# reamiga_1200_mouse_USB_v1.net
KiCad netlist of a schematic drawn in EAGLE
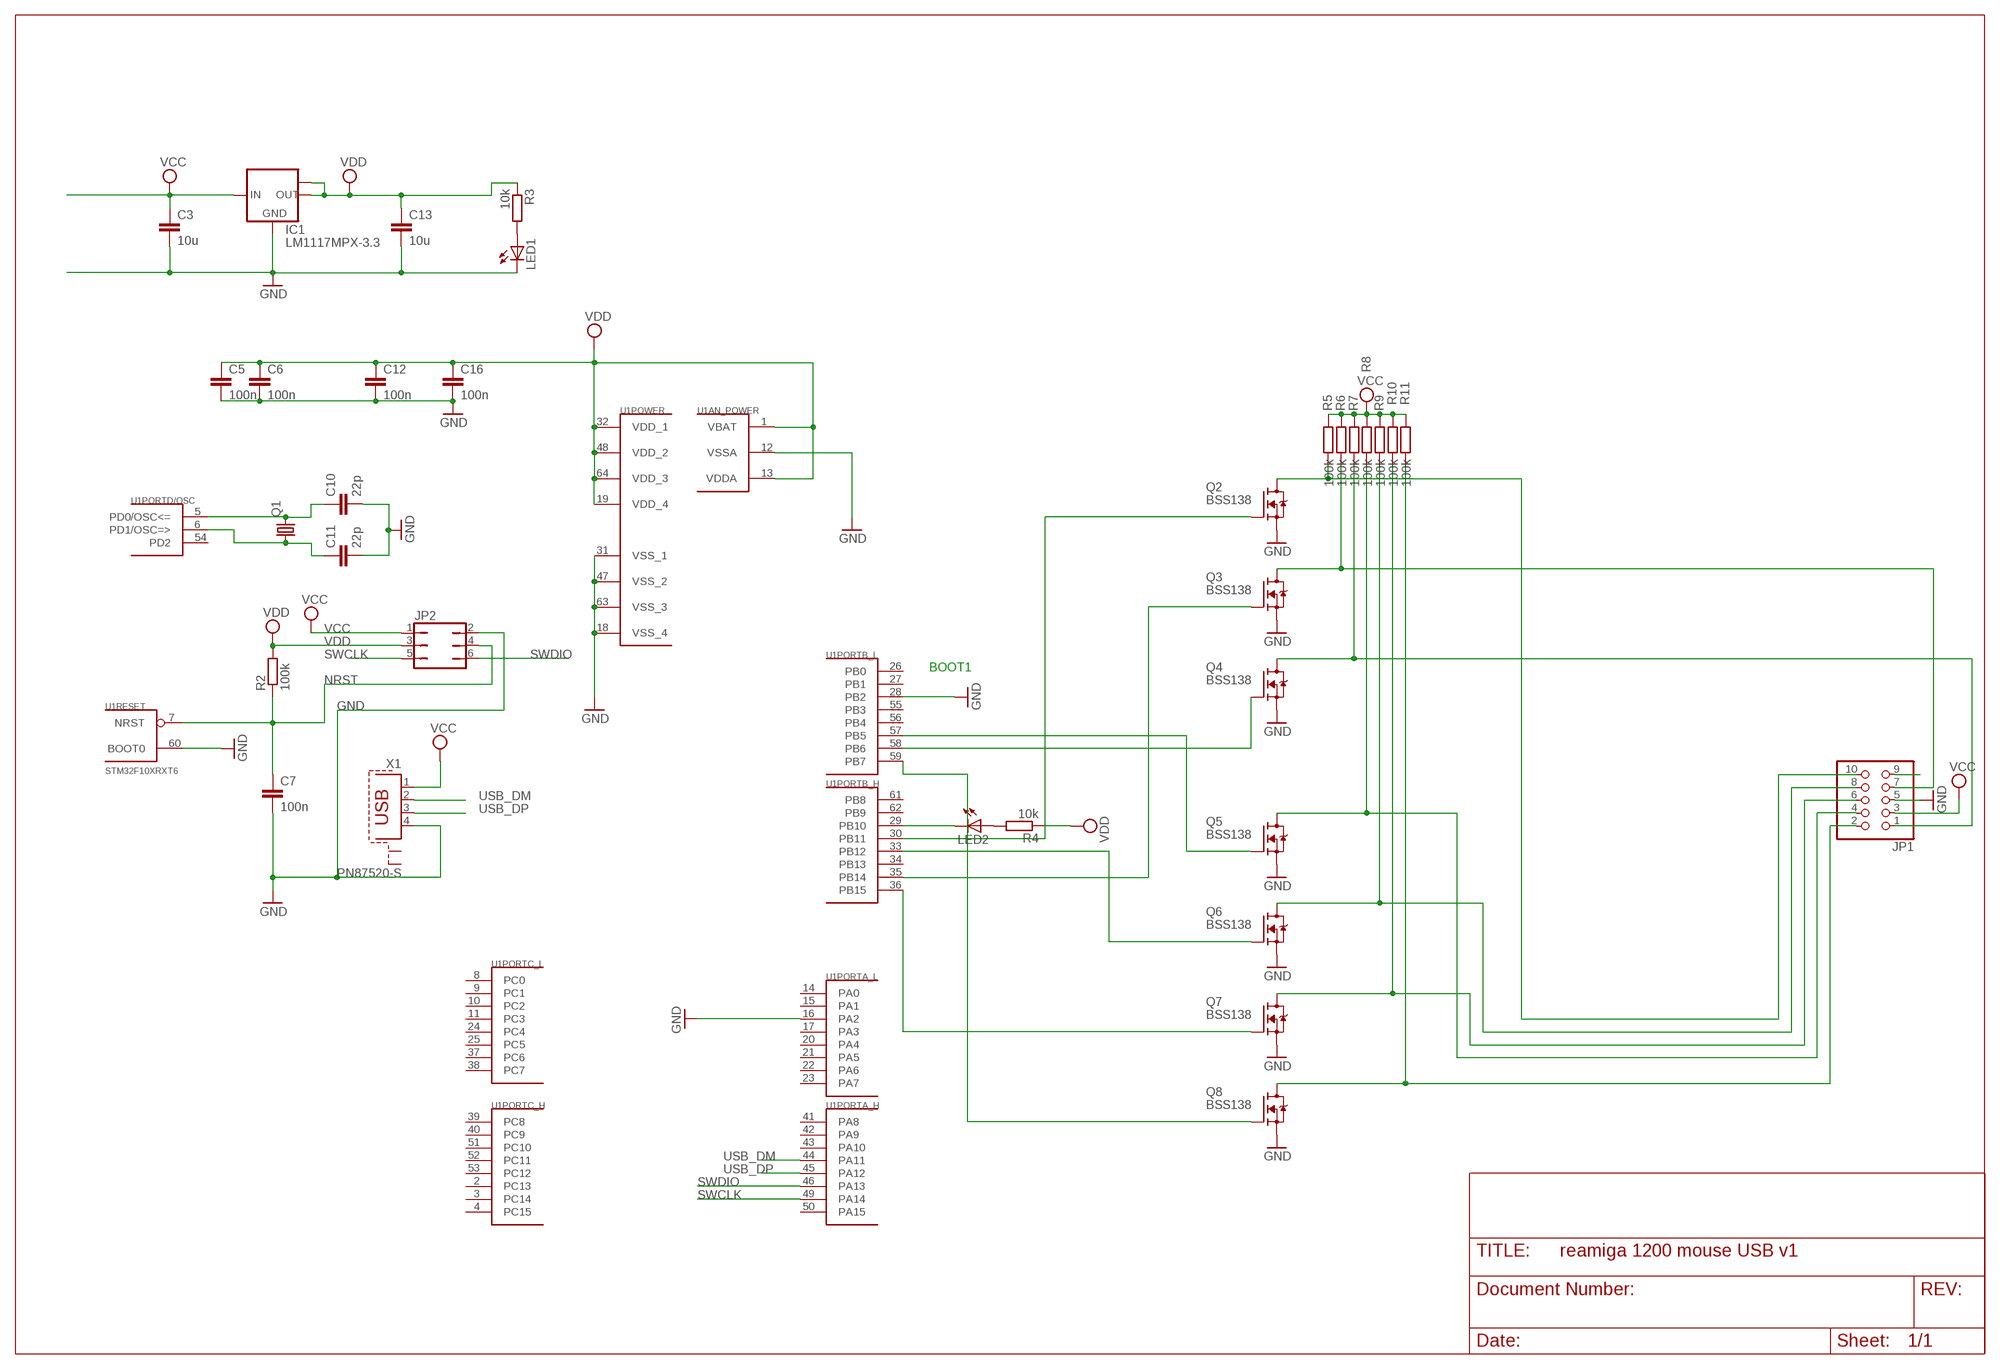
[diagram p0: schematic, sheet 1]

(export (version "E")
  (design (tool "Eeschema 10.0.6"))
  (components
    (comp (ref "C3")
      (value "10u")
      (footprint "eagle-import:C1206")
      (libsource (lib "eagle-import") (part "C-EUC1206"))
    )
    (comp (ref "C5")
      (value "100n")
      (footprint "eagle-import:C0603")
      (libsource (lib "eagle-import") (part "C-EUC0603"))
    )
    (comp (ref "C6")
      (value "100n")
      (footprint "eagle-import:C0603")
      (libsource (lib "eagle-import") (part "C-EUC0603"))
    )
    (comp (ref "C7")
      (value "100n")
      (footprint "eagle-import:C0603")
      (libsource (lib "eagle-import") (part "C-EUC0603"))
    )
    (comp (ref "C10")
      (value "22p")
      (footprint "eagle-import:C0603")
      (libsource (lib "eagle-import") (part "C-EUC0603"))
    )
    (comp (ref "C11")
      (value "22p")
      (footprint "eagle-import:C0603")
      (libsource (lib "eagle-import") (part "C-EUC0603"))
    )
    (comp (ref "C12")
      (value "100n")
      (footprint "eagle-import:C0603")
      (libsource (lib "eagle-import") (part "C-EUC0603"))
    )
    (comp (ref "C13")
      (value "10u")
      (footprint "eagle-import:C1206")
      (libsource (lib "eagle-import") (part "C-EUC1206"))
    )
    (comp (ref "C16")
      (value "100n")
      (footprint "eagle-import:C0603")
      (libsource (lib "eagle-import") (part "C-EUC0603"))
    )
    (comp (ref "IC1")
      (value "LM1117MPX-3.3")
      (footprint "eagle-import:SOT223")
      (libsource (lib "eagle-import") (part "LM1117MPX-3.3"))
    )
    (comp (ref "JP1")
      (value "PINHD-2X5")
      (footprint "eagle-import:2X05")
      (libsource (lib "eagle-import") (part "PINHD-2X5"))
    )
    (comp (ref "JP2")
      (value "JP3Q")
      (footprint "eagle-import:JP3Q")
      (libsource (lib "eagle-import") (part "JP3Q"))
    )
    (comp (ref "LED1")
      (value "LEDSML0805")
      (footprint "eagle-import:SML0805")
      (libsource (lib "eagle-import") (part "LEDSML0805"))
    )
    (comp (ref "LED2")
      (value "LEDSML0805")
      (footprint "eagle-import:SML0805")
      (libsource (lib "eagle-import") (part "LEDSML0805"))
    )
    (comp (ref "Q1")
      (value "CRYSTALHC49S")
      (footprint "eagle-import:HC49_S")
      (libsource (lib "eagle-import") (part "CRYSTALHC49S"))
    )
    (comp (ref "Q2")
      (value "BSS138")
      (footprint "eagle-import:SOT23")
      (fields (field (name "MF") "Fairchild"))
      (libsource (lib "eagle-import") (part "BSS138"))
    )
    (comp (ref "Q3")
      (value "BSS138")
      (footprint "eagle-import:SOT23")
      (fields (field (name "MF") "Fairchild"))
      (libsource (lib "eagle-import") (part "BSS138"))
    )
    (comp (ref "Q4")
      (value "BSS138")
      (footprint "eagle-import:SOT23")
      (fields (field (name "MF") "Fairchild"))
      (libsource (lib "eagle-import") (part "BSS138"))
    )
    (comp (ref "Q5")
      (value "BSS138")
      (footprint "eagle-import:SOT23")
      (fields (field (name "MF") "Fairchild"))
      (libsource (lib "eagle-import") (part "BSS138"))
    )
    (comp (ref "Q6")
      (value "BSS138")
      (footprint "eagle-import:SOT23")
      (fields (field (name "MF") "Fairchild"))
      (libsource (lib "eagle-import") (part "BSS138"))
    )
    (comp (ref "Q7")
      (value "BSS138")
      (footprint "eagle-import:SOT23")
      (fields (field (name "MF") "Fairchild"))
      (libsource (lib "eagle-import") (part "BSS138"))
    )
    (comp (ref "Q8")
      (value "BSS138")
      (footprint "eagle-import:SOT23")
      (fields (field (name "MF") "Fairchild"))
      (libsource (lib "eagle-import") (part "BSS138"))
    )
    (comp (ref "R2")
      (value "100k")
      (footprint "eagle-import:R0603")
      (libsource (lib "eagle-import") (part "R-EU_R0603"))
    )
    (comp (ref "R3")
      (value "10k")
      (footprint "eagle-import:R0603")
      (libsource (lib "eagle-import") (part "R-EU_R0603"))
    )
    (comp (ref "R4")
      (value "10k")
      (footprint "eagle-import:R0603")
      (libsource (lib "eagle-import") (part "R-EU_R0603"))
    )
    (comp (ref "R5")
      (value "100k")
      (footprint "eagle-import:R0603")
      (libsource (lib "eagle-import") (part "R-EU_R0603"))
    )
    (comp (ref "R6")
      (value "100k")
      (footprint "eagle-import:R0603")
      (libsource (lib "eagle-import") (part "R-EU_R0603"))
    )
    (comp (ref "R7")
      (value "100k")
      (footprint "eagle-import:R0603")
      (libsource (lib "eagle-import") (part "R-EU_R0603"))
    )
    (comp (ref "R8")
      (value "100k")
      (footprint "eagle-import:R0603")
      (libsource (lib "eagle-import") (part "R-EU_R0603"))
    )
    (comp (ref "R9")
      (value "100k")
      (footprint "eagle-import:R0603")
      (libsource (lib "eagle-import") (part "R-EU_R0603"))
    )
    (comp (ref "R10")
      (value "100k")
      (footprint "eagle-import:R0603")
      (libsource (lib "eagle-import") (part "R-EU_R0603"))
    )
    (comp (ref "R11")
      (value "100k")
      (footprint "eagle-import:R0603")
      (libsource (lib "eagle-import") (part "R-EU_R0603"))
    )
    (comp (ref "U1")
      (value "STM32F10XRXT6")
      (footprint "eagle-import:TQFP64")
      (libsource (lib "eagle-import") (part "STM32F10XRXT6"))
    )
    (comp (ref "X1")
      (value "PN87520-S")
      (footprint "eagle-import:PN87520-S")
      (libsource (lib "eagle-import") (part "PN87520-S"))
    )
  )
  (nets
    (net (code "1") (name "/NRST") (class "Default")
      (node (ref "C7") (pin "1") (pinfunction "1_1") (pintype "passive"))
      (node (ref "JP2") (pin "4") (pinfunction "4_4") (pintype "passive"))
      (node (ref "R2") (pin "1") (pinfunction "1_1") (pintype "passive"))
      (node (ref "U1") (pin "7") (pinfunction "NRST_7") (pintype "input"))
    )
    (net (code "2") (name "/SWCLK") (class "Default")
      (node (ref "JP2") (pin "5") (pinfunction "5_5") (pintype "passive"))
      (node (ref "U1") (pin "49") (pinfunction "PA14_49") (pintype "bidirectional"))
    )
    (net (code "3") (name "/SWDIO") (class "Default")
      (node (ref "JP2") (pin "6") (pinfunction "6_6") (pintype "passive"))
      (node (ref "U1") (pin "46") (pinfunction "PA13_46") (pintype "bidirectional"))
    )
    (net (code "4") (name "/USB_DM") (class "Default")
      (node (ref "U1") (pin "44") (pinfunction "PA11_44") (pintype "bidirectional"))
      (node (ref "X1") (pin "2") (pinfunction "2_2") (pintype "passive"))
    )
    (net (code "5") (name "/USB_DP") (class "Default")
      (node (ref "U1") (pin "45") (pinfunction "PA12_45") (pintype "bidirectional"))
      (node (ref "X1") (pin "3") (pinfunction "3_3") (pintype "passive"))
    )
    (net (code "6") (name "GND") (class "Default")
      (node (ref "C10") (pin "2") (pinfunction "2_2") (pintype "passive"))
      (node (ref "C11") (pin "2") (pinfunction "2_2") (pintype "passive"))
      (node (ref "C12") (pin "2") (pinfunction "2_2") (pintype "passive"))
      (node (ref "C13") (pin "2") (pinfunction "2_2") (pintype "passive"))
      (node (ref "C16") (pin "2") (pinfunction "2_2") (pintype "passive"))
      (node (ref "C3") (pin "2") (pinfunction "2_2") (pintype "passive"))
      (node (ref "C5") (pin "2") (pinfunction "2_2") (pintype "passive"))
      (node (ref "C6") (pin "2") (pinfunction "2_2") (pintype "passive"))
      (node (ref "C7") (pin "2") (pinfunction "2_2") (pintype "passive"))
      (node (ref "IC1") (pin "1") (pinfunction "GND_1") (pintype "input"))
      (node (ref "JP1") (pin "5") (pinfunction "5_5") (pintype "passive"))
      (node (ref "JP2") (pin "2") (pinfunction "2_2") (pintype "passive"))
      (node (ref "LED1") (pin "C") (pinfunction "C_C") (pintype "passive"))
      (node (ref "Q2") (pin "2") (pinfunction "S_2") (pintype "passive"))
      (node (ref "Q3") (pin "2") (pinfunction "S_2") (pintype "passive"))
      (node (ref "Q4") (pin "2") (pinfunction "S_2") (pintype "passive"))
      (node (ref "Q5") (pin "2") (pinfunction "S_2") (pintype "passive"))
      (node (ref "Q6") (pin "2") (pinfunction "S_2") (pintype "passive"))
      (node (ref "Q7") (pin "2") (pinfunction "S_2") (pintype "passive"))
      (node (ref "Q8") (pin "2") (pinfunction "S_2") (pintype "passive"))
      (node (ref "U1") (pin "12") (pinfunction "VSSA_12") (pintype "power_in"))
      (node (ref "U1") (pin "16") (pinfunction "PA2_16") (pintype "bidirectional"))
      (node (ref "U1") (pin "18") (pinfunction "VSS_4_18") (pintype "power_in"))
      (node (ref "U1") (pin "28") (pinfunction "PB2_28") (pintype "bidirectional"))
      (node (ref "U1") (pin "31") (pinfunction "VSS_1_31") (pintype "power_in"))
      (node (ref "U1") (pin "47") (pinfunction "VSS_2_47") (pintype "power_in"))
      (node (ref "U1") (pin "60") (pinfunction "BOOT0_60") (pintype "input"))
      (node (ref "U1") (pin "63") (pinfunction "VSS_3_63") (pintype "power_in"))
      (node (ref "X1") (pin "4") (pinfunction "4_4") (pintype "passive"))
    )
    (net (code "7") (name "Net-(LED1-PadA)") (class "Default")
      (node (ref "LED1") (pin "A") (pinfunction "A_A") (pintype "passive"))
      (node (ref "R3") (pin "2") (pinfunction "2_2") (pintype "passive"))
    )
    (net (code "8") (name "Net-(LED2-PadA)") (class "Default")
      (node (ref "LED2") (pin "A") (pinfunction "A_A") (pintype "passive"))
      (node (ref "R4") (pin "2") (pinfunction "2_2") (pintype "passive"))
    )
    (net (code "9") (name "Net-(Q2-D)") (class "Default")
      (node (ref "JP1") (pin "10") (pinfunction "10_10") (pintype "passive"))
      (node (ref "Q2") (pin "3") (pinfunction "D_3") (pintype "passive"))
      (node (ref "R5") (pin "2") (pinfunction "2_2") (pintype "passive"))
    )
    (net (code "10") (name "Net-(Q2-G)") (class "Default")
      (node (ref "Q2") (pin "1") (pinfunction "G_1") (pintype "passive"))
      (node (ref "U1") (pin "30") (pinfunction "PB11_30") (pintype "bidirectional"))
    )
    (net (code "11") (name "Net-(Q3-D)") (class "Default")
      (node (ref "JP1") (pin "7") (pinfunction "7_7") (pintype "passive"))
      (node (ref "Q3") (pin "3") (pinfunction "D_3") (pintype "passive"))
      (node (ref "R6") (pin "2") (pinfunction "2_2") (pintype "passive"))
    )
    (net (code "12") (name "Net-(Q3-G)") (class "Default")
      (node (ref "Q3") (pin "1") (pinfunction "G_1") (pintype "passive"))
      (node (ref "U1") (pin "35") (pinfunction "PB14_35") (pintype "bidirectional"))
    )
    (net (code "13") (name "Net-(Q4-D)") (class "Default")
      (node (ref "JP1") (pin "1") (pinfunction "1_1") (pintype "passive"))
      (node (ref "Q4") (pin "3") (pinfunction "D_3") (pintype "passive"))
      (node (ref "R7") (pin "2") (pinfunction "2_2") (pintype "passive"))
    )
    (net (code "14") (name "Net-(Q4-G)") (class "Default")
      (node (ref "Q4") (pin "1") (pinfunction "G_1") (pintype "passive"))
      (node (ref "U1") (pin "58") (pinfunction "PB6_58") (pintype "bidirectional"))
    )
    (net (code "15") (name "Net-(Q5-D)") (class "Default")
      (node (ref "JP1") (pin "4") (pinfunction "4_4") (pintype "passive"))
      (node (ref "Q5") (pin "3") (pinfunction "D_3") (pintype "passive"))
      (node (ref "R8") (pin "2") (pinfunction "2_2") (pintype "passive"))
    )
    (net (code "16") (name "Net-(Q5-G)") (class "Default")
      (node (ref "Q5") (pin "1") (pinfunction "G_1") (pintype "passive"))
      (node (ref "U1") (pin "57") (pinfunction "PB5_57") (pintype "bidirectional"))
    )
    (net (code "17") (name "Net-(Q6-D)") (class "Default")
      (node (ref "JP1") (pin "8") (pinfunction "8_8") (pintype "passive"))
      (node (ref "Q6") (pin "3") (pinfunction "D_3") (pintype "passive"))
      (node (ref "R9") (pin "2") (pinfunction "2_2") (pintype "passive"))
    )
    (net (code "18") (name "Net-(Q6-G)") (class "Default")
      (node (ref "Q6") (pin "1") (pinfunction "G_1") (pintype "passive"))
      (node (ref "U1") (pin "33") (pinfunction "PB12_33") (pintype "bidirectional"))
    )
    (net (code "19") (name "Net-(Q7-D)") (class "Default")
      (node (ref "JP1") (pin "6") (pinfunction "6_6") (pintype "passive"))
      (node (ref "Q7") (pin "3") (pinfunction "D_3") (pintype "passive"))
      (node (ref "R10") (pin "2") (pinfunction "2_2") (pintype "passive"))
    )
    (net (code "20") (name "Net-(Q7-G)") (class "Default")
      (node (ref "Q7") (pin "1") (pinfunction "G_1") (pintype "passive"))
      (node (ref "U1") (pin "36") (pinfunction "PB15_36") (pintype "bidirectional"))
    )
    (net (code "21") (name "Net-(Q8-D)") (class "Default")
      (node (ref "JP1") (pin "2") (pinfunction "2_2") (pintype "passive"))
      (node (ref "Q8") (pin "3") (pinfunction "D_3") (pintype "passive"))
      (node (ref "R11") (pin "2") (pinfunction "2_2") (pintype "passive"))
    )
    (net (code "22") (name "Net-(Q8-G)") (class "Default")
      (node (ref "Q8") (pin "1") (pinfunction "G_1") (pintype "passive"))
      (node (ref "U1") (pin "59") (pinfunction "PB7_59") (pintype "bidirectional"))
    )
    (net (code "23") (name "Net-(U1D-PB10)") (class "Default")
      (node (ref "LED2") (pin "C") (pinfunction "C_C") (pintype "passive"))
      (node (ref "U1") (pin "29") (pinfunction "PB10_29") (pintype "bidirectional"))
    )
    (net (code "24") (name "Net-(U1H-PD0{slash}OSC<=)") (class "Default")
      (node (ref "C10") (pin "1") (pinfunction "1_1") (pintype "passive"))
      (node (ref "Q1") (pin "2") (pinfunction "2_2") (pintype "passive"))
      (node (ref "U1") (pin "5") (pinfunction "PD0/OSC<=_5") (pintype "bidirectional"))
    )
    (net (code "25") (name "Net-(U1H-PD1{slash}OSC=>)") (class "Default")
      (node (ref "C11") (pin "1") (pinfunction "1_1") (pintype "passive"))
      (node (ref "Q1") (pin "1") (pinfunction "1_1") (pintype "passive"))
      (node (ref "U1") (pin "6") (pinfunction "PD1/OSC=>_6") (pintype "bidirectional"))
    )
    (net (code "26") (name "VCC") (class "Default")
      (node (ref "C3") (pin "1") (pinfunction "1_1") (pintype "passive"))
      (node (ref "IC1") (pin "3") (pinfunction "IN_3") (pintype "input"))
      (node (ref "JP1") (pin "3") (pinfunction "3_3") (pintype "passive"))
      (node (ref "JP2") (pin "1") (pinfunction "1_1") (pintype "passive"))
      (node (ref "R10") (pin "1") (pinfunction "1_1") (pintype "passive"))
      (node (ref "R11") (pin "1") (pinfunction "1_1") (pintype "passive"))
      (node (ref "R5") (pin "1") (pinfunction "1_1") (pintype "passive"))
      (node (ref "R6") (pin "1") (pinfunction "1_1") (pintype "passive"))
      (node (ref "R7") (pin "1") (pinfunction "1_1") (pintype "passive"))
      (node (ref "R8") (pin "1") (pinfunction "1_1") (pintype "passive"))
      (node (ref "R9") (pin "1") (pinfunction "1_1") (pintype "passive"))
      (node (ref "X1") (pin "1") (pinfunction "1_1") (pintype "passive"))
    )
    (net (code "27") (name "VDD") (class "Default")
      (node (ref "C12") (pin "1") (pinfunction "1_1") (pintype "passive"))
      (node (ref "C13") (pin "1") (pinfunction "1_1") (pintype "passive"))
      (node (ref "C16") (pin "1") (pinfunction "1_1") (pintype "passive"))
      (node (ref "C5") (pin "1") (pinfunction "1_1") (pintype "passive"))
      (node (ref "C6") (pin "1") (pinfunction "1_1") (pintype "passive"))
      (node (ref "IC1") (pin "2") (pinfunction "OUT_2") (pintype "passive"))
      (node (ref "IC1") (pin "TAB") (pinfunction "OUT1_TAB") (pintype "passive"))
      (node (ref "JP2") (pin "3") (pinfunction "3_3") (pintype "passive"))
      (node (ref "R2") (pin "2") (pinfunction "2_2") (pintype "passive"))
      (node (ref "R3") (pin "1") (pinfunction "1_1") (pintype "passive"))
      (node (ref "R4") (pin "1") (pinfunction "1_1") (pintype "passive"))
      (node (ref "U1") (pin "1") (pinfunction "VBAT_1") (pintype "power_in"))
      (node (ref "U1") (pin "13") (pinfunction "VDDA_13") (pintype "power_in"))
      (node (ref "U1") (pin "19") (pinfunction "VDD_4_19") (pintype "power_in"))
      (node (ref "U1") (pin "32") (pinfunction "VDD_1_32") (pintype "power_in"))
      (node (ref "U1") (pin "48") (pinfunction "VDD_2_48") (pintype "power_in"))
      (node (ref "U1") (pin "64") (pinfunction "VDD_3_64") (pintype "power_in"))
    )
    (net (code "28") (name "unconnected-(JP1-Pad9)") (class "Default")
      (node (ref "JP1") (pin "9") (pinfunction "9_9") (pintype "passive"))
    )
    (net (code "29") (name "unconnected-(U1B-PA8-Pad41)") (class "Default")
      (node (ref "U1") (pin "41") (pinfunction "PA8_41") (pintype "bidirectional"))
    )
    (net (code "30") (name "unconnected-(U1B-PA9-Pad42)") (class "Default")
      (node (ref "U1") (pin "42") (pinfunction "PA9_42") (pintype "bidirectional"))
    )
    (net (code "31") (name "unconnected-(U1B-PA10-Pad43)") (class "Default")
      (node (ref "U1") (pin "43") (pinfunction "PA10_43") (pintype "bidirectional"))
    )
    (net (code "32") (name "unconnected-(U1B-PA15-Pad50)") (class "Default")
      (node (ref "U1") (pin "50") (pinfunction "PA15_50") (pintype "bidirectional"))
    )
    (net (code "33") (name "unconnected-(U1C-PA0-Pad14)") (class "Default")
      (node (ref "U1") (pin "14") (pinfunction "PA0_14") (pintype "bidirectional"))
    )
    (net (code "34") (name "unconnected-(U1C-PA1-Pad15)") (class "Default")
      (node (ref "U1") (pin "15") (pinfunction "PA1_15") (pintype "bidirectional"))
    )
    (net (code "35") (name "unconnected-(U1C-PA3-Pad17)") (class "Default")
      (node (ref "U1") (pin "17") (pinfunction "PA3_17") (pintype "bidirectional"))
    )
    (net (code "36") (name "unconnected-(U1C-PA4-Pad20)") (class "Default")
      (node (ref "U1") (pin "20") (pinfunction "PA4_20") (pintype "bidirectional"))
    )
    (net (code "37") (name "unconnected-(U1C-PA5-Pad21)") (class "Default")
      (node (ref "U1") (pin "21") (pinfunction "PA5_21") (pintype "bidirectional"))
    )
    (net (code "38") (name "unconnected-(U1C-PA6-Pad22)") (class "Default")
      (node (ref "U1") (pin "22") (pinfunction "PA6_22") (pintype "bidirectional"))
    )
    (net (code "39") (name "unconnected-(U1C-PA7-Pad23)") (class "Default")
      (node (ref "U1") (pin "23") (pinfunction "PA7_23") (pintype "bidirectional"))
    )
    (net (code "40") (name "unconnected-(U1D-PB8-Pad61)") (class "Default")
      (node (ref "U1") (pin "61") (pinfunction "PB8_61") (pintype "bidirectional"))
    )
    (net (code "41") (name "unconnected-(U1D-PB9-Pad62)") (class "Default")
      (node (ref "U1") (pin "62") (pinfunction "PB9_62") (pintype "bidirectional"))
    )
    (net (code "42") (name "unconnected-(U1D-PB13-Pad34)") (class "Default")
      (node (ref "U1") (pin "34") (pinfunction "PB13_34") (pintype "bidirectional"))
    )
    (net (code "43") (name "unconnected-(U1E-PB0-Pad26)") (class "Default")
      (node (ref "U1") (pin "26") (pinfunction "PB0_26") (pintype "bidirectional"))
    )
    (net (code "44") (name "unconnected-(U1E-PB1-Pad27)") (class "Default")
      (node (ref "U1") (pin "27") (pinfunction "PB1_27") (pintype "bidirectional"))
    )
    (net (code "45") (name "unconnected-(U1E-PB3-Pad55)") (class "Default")
      (node (ref "U1") (pin "55") (pinfunction "PB3_55") (pintype "bidirectional"))
    )
    (net (code "46") (name "unconnected-(U1E-PB4-Pad56)") (class "Default")
      (node (ref "U1") (pin "56") (pinfunction "PB4_56") (pintype "bidirectional"))
    )
    (net (code "47") (name "unconnected-(U1F-PC8-Pad39)") (class "Default")
      (node (ref "U1") (pin "39") (pinfunction "PC8_39") (pintype "bidirectional"))
    )
    (net (code "48") (name "unconnected-(U1F-PC9-Pad40)") (class "Default")
      (node (ref "U1") (pin "40") (pinfunction "PC9_40") (pintype "bidirectional"))
    )
    (net (code "49") (name "unconnected-(U1F-PC10-Pad51)") (class "Default")
      (node (ref "U1") (pin "51") (pinfunction "PC10_51") (pintype "bidirectional"))
    )
    (net (code "50") (name "unconnected-(U1F-PC11-Pad52)") (class "Default")
      (node (ref "U1") (pin "52") (pinfunction "PC11_52") (pintype "bidirectional"))
    )
    (net (code "51") (name "unconnected-(U1F-PC12-Pad53)") (class "Default")
      (node (ref "U1") (pin "53") (pinfunction "PC12_53") (pintype "bidirectional"))
    )
    (net (code "52") (name "unconnected-(U1F-PC13-Pad2)") (class "Default")
      (node (ref "U1") (pin "2") (pinfunction "PC13_2") (pintype "bidirectional"))
    )
    (net (code "53") (name "unconnected-(U1F-PC14-Pad3)") (class "Default")
      (node (ref "U1") (pin "3") (pinfunction "PC14_3") (pintype "bidirectional"))
    )
    (net (code "54") (name "unconnected-(U1F-PC15-Pad4)") (class "Default")
      (node (ref "U1") (pin "4") (pinfunction "PC15_4") (pintype "bidirectional"))
    )
    (net (code "55") (name "unconnected-(U1G-PC0-Pad8)") (class "Default")
      (node (ref "U1") (pin "8") (pinfunction "PC0_8") (pintype "bidirectional"))
    )
    (net (code "56") (name "unconnected-(U1G-PC1-Pad9)") (class "Default")
      (node (ref "U1") (pin "9") (pinfunction "PC1_9") (pintype "bidirectional"))
    )
    (net (code "57") (name "unconnected-(U1G-PC2-Pad10)") (class "Default")
      (node (ref "U1") (pin "10") (pinfunction "PC2_10") (pintype "bidirectional"))
    )
    (net (code "58") (name "unconnected-(U1G-PC3-Pad11)") (class "Default")
      (node (ref "U1") (pin "11") (pinfunction "PC3_11") (pintype "bidirectional"))
    )
    (net (code "59") (name "unconnected-(U1G-PC4-Pad24)") (class "Default")
      (node (ref "U1") (pin "24") (pinfunction "PC4_24") (pintype "bidirectional"))
    )
    (net (code "60") (name "unconnected-(U1G-PC5-Pad25)") (class "Default")
      (node (ref "U1") (pin "25") (pinfunction "PC5_25") (pintype "bidirectional"))
    )
    (net (code "61") (name "unconnected-(U1G-PC6-Pad37)") (class "Default")
      (node (ref "U1") (pin "37") (pinfunction "PC6_37") (pintype "bidirectional"))
    )
    (net (code "62") (name "unconnected-(U1G-PC7-Pad38)") (class "Default")
      (node (ref "U1") (pin "38") (pinfunction "PC7_38") (pintype "bidirectional"))
    )
    (net (code "63") (name "unconnected-(U1H-PD2-Pad54)") (class "Default")
      (node (ref "U1") (pin "54") (pinfunction "PD2_54") (pintype "bidirectional"))
    )
    (net (code "64") (name "unconnected-(X1-PadS1)") (class "Default")
      (node (ref "X1") (pin "S1") (pinfunction "S1_S1") (pintype "passive"))
    )
    (net (code "65") (name "unconnected-(X1-PadS2)") (class "Default")
      (node (ref "X1") (pin "S2") (pinfunction "S2_S2") (pintype "passive"))
    )
  )
)
